# slot_stm32f4.net
KiCad netlist of a schematic drawn in EAGLE
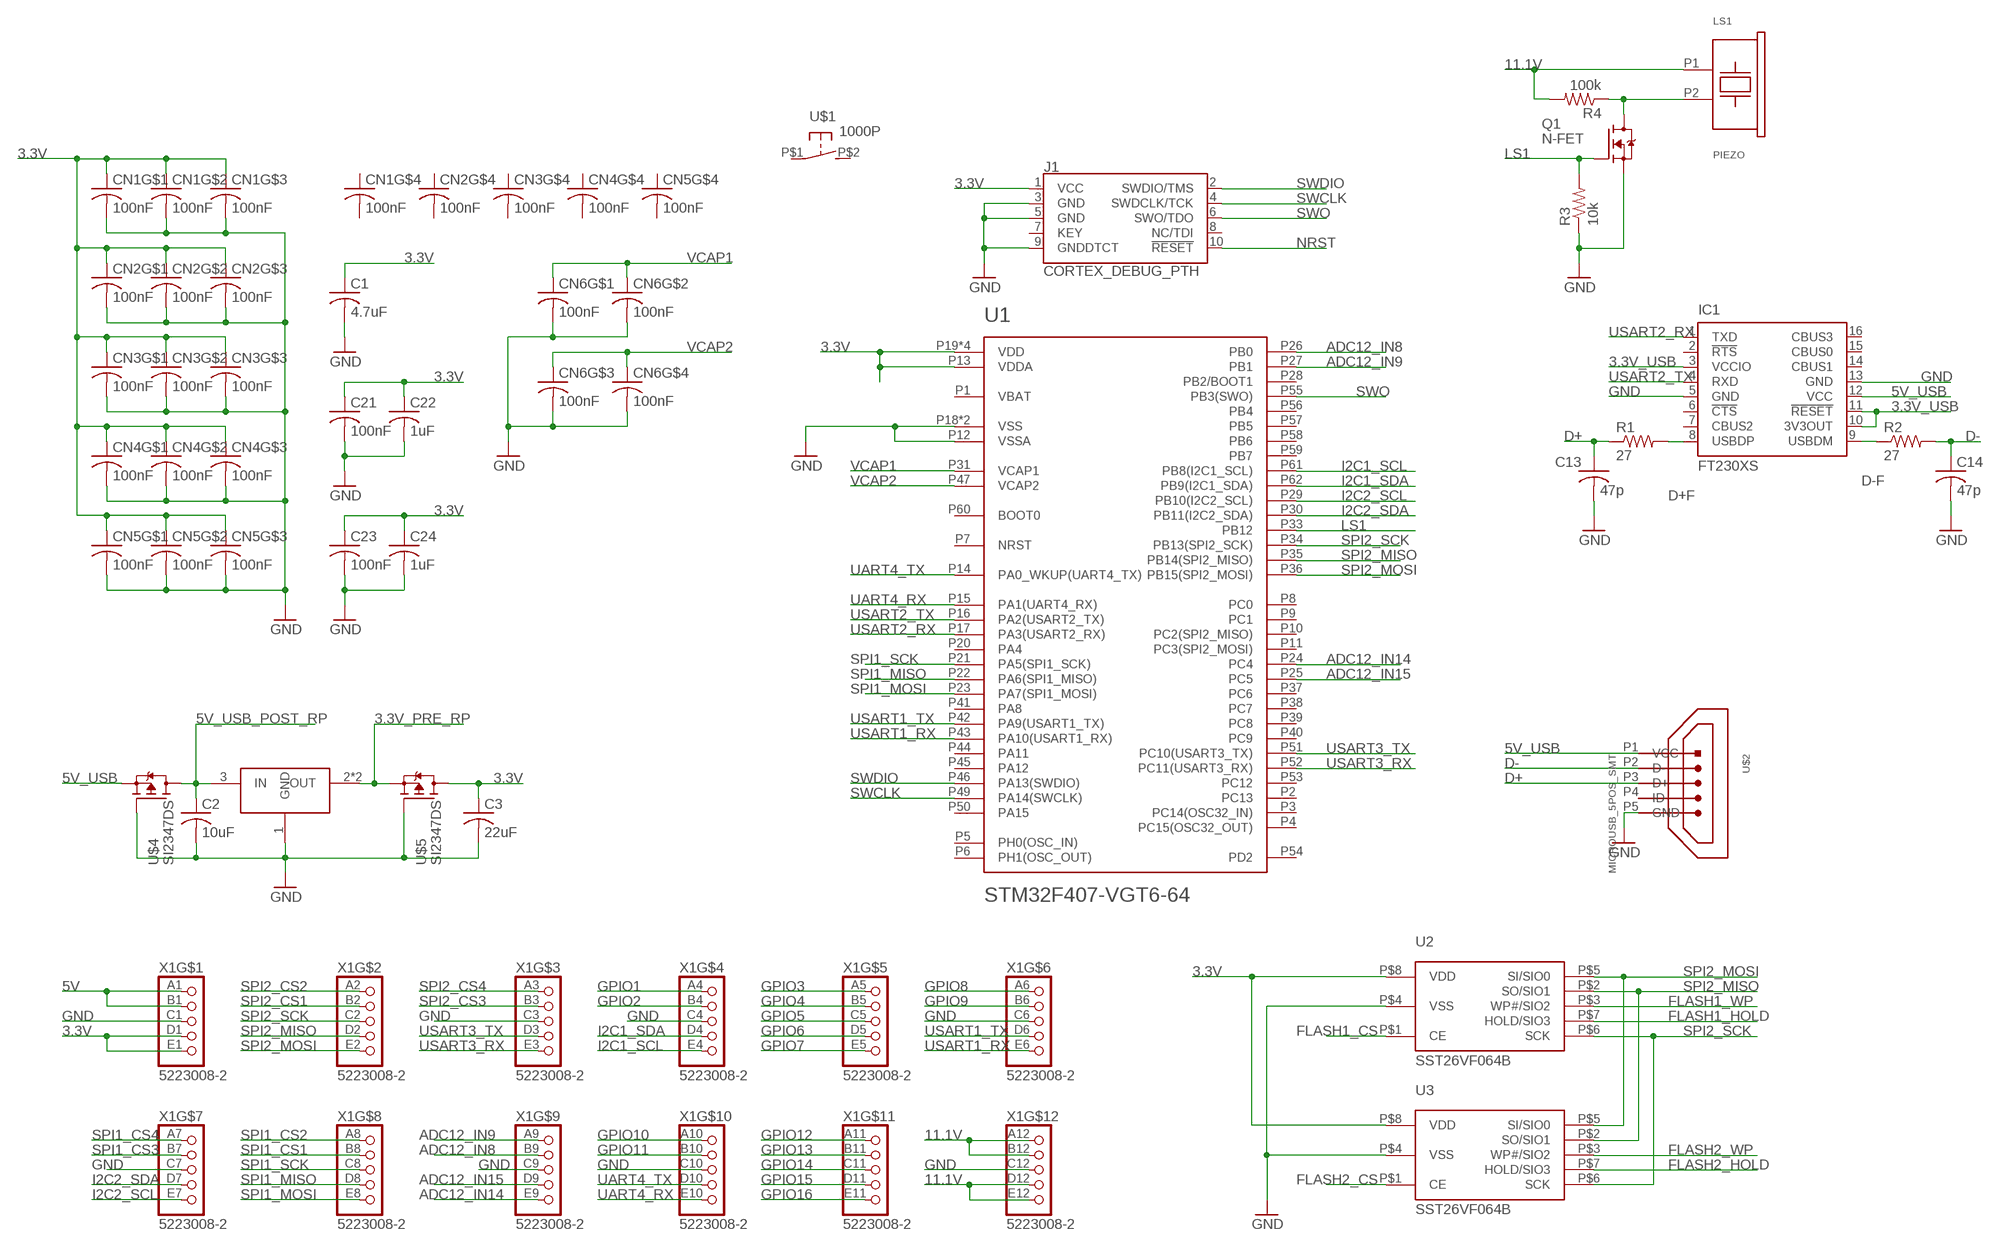
[diagram p0: schematic, sheet 1]

(export (version "E")
  (design (tool "Eeschema 10.0.6"))
  (components
    (comp (ref "C1")
      (value "4.7uF")
      (footprint "eagle-import:C0805")
      (libsource (lib "eagle-import") (part "C-USC0805"))
    )
    (comp (ref "C2")
      (value "10uF")
      (footprint "eagle-import:C0805")
      (libsource (lib "eagle-import") (part "C-USC0805"))
    )
    (comp (ref "C3")
      (value "22uF")
      (footprint "eagle-import:C0805")
      (libsource (lib "eagle-import") (part "C-USC0805"))
    )
    (comp (ref "C13")
      (value "47p")
      (footprint "eagle-import:C0603")
      (libsource (lib "eagle-import") (part "resistor_348_C-USC0603"))
    )
    (comp (ref "C14")
      (value "47p")
      (footprint "eagle-import:C0603")
      (libsource (lib "eagle-import") (part "resistor_348_C-USC0603"))
    )
    (comp (ref "C21")
      (value "100nF")
      (footprint "eagle-import:C0805")
      (libsource (lib "eagle-import") (part "C-USC0805"))
    )
    (comp (ref "C22")
      (value "1uF")
      (footprint "eagle-import:C0805")
      (libsource (lib "eagle-import") (part "C-USC0805"))
    )
    (comp (ref "C23")
      (value "100nF")
      (footprint "eagle-import:C0805")
      (libsource (lib "eagle-import") (part "C-USC0805"))
    )
    (comp (ref "C24")
      (value "1uF")
      (footprint "eagle-import:C0805")
      (libsource (lib "eagle-import") (part "C-USC0805"))
    )
    (comp (ref "CN1")
      (value "100nF")
      (footprint "eagle-import:CNET_4POS_0612")
      (libsource (lib "eagle-import") (part "CA064CXXXXXRAC"))
    )
    (comp (ref "CN2")
      (value "100nF")
      (footprint "eagle-import:CNET_4POS_0612")
      (libsource (lib "eagle-import") (part "CA064CXXXXXRAC"))
    )
    (comp (ref "CN3")
      (value "100nF")
      (footprint "eagle-import:CNET_4POS_0612")
      (libsource (lib "eagle-import") (part "CA064CXXXXXRAC"))
    )
    (comp (ref "CN4")
      (value "100nF")
      (footprint "eagle-import:CNET_4POS_0612")
      (libsource (lib "eagle-import") (part "CA064CXXXXXRAC"))
    )
    (comp (ref "CN5")
      (value "100nF")
      (footprint "eagle-import:CNET_4POS_0612")
      (libsource (lib "eagle-import") (part "CA064CXXXXXRAC"))
    )
    (comp (ref "CN6")
      (value "100nF")
      (footprint "eagle-import:CNET_4POS_0612")
      (libsource (lib "eagle-import") (part "CA064CXXXXXRAC"))
    )
    (comp (ref "IC1")
      (value "FT230XS")
      (footprint "eagle-import:SSOP16")
      (libsource (lib "eagle-import") (part "FT230XS"))
    )
    (comp (ref "J1")
      (value "CORTEX_DEBUG_PTH")
      (footprint "eagle-import:2X5-PTH-1.27MM")
      (libsource (lib "eagle-import") (part "CORTEX_DEBUG_PTH"))
    )
    (comp (ref "LS1")
      (value "PIEZO")
      (footprint "eagle-import:PKMCS0909E400-R1")
      (libsource (lib "eagle-import") (part "PIEZO"))
    )
    (comp (ref "Q1")
      (value "N-FET")
      (footprint "eagle-import:NMINI3-R1-B")
      (libsource (lib "eagle-import") (part "N-FET"))
    )
    (comp (ref "R1")
      (value "27")
      (footprint "eagle-import:R0603")
      (libsource (lib "eagle-import") (part "R-US_R0603"))
    )
    (comp (ref "R2")
      (value "27")
      (footprint "eagle-import:R0603")
      (libsource (lib "eagle-import") (part "R-US_R0603"))
    )
    (comp (ref "R3")
      (value "10k")
      (footprint "eagle-import:R0603")
      (libsource (lib "eagle-import") (part "R-US_R0603"))
    )
    (comp (ref "R4")
      (value "100k")
      (footprint "eagle-import:R0603")
      (libsource (lib "eagle-import") (part "R-US_R0603"))
    )
    (comp (ref "U$1")
      (value "1000P")
      (footprint "eagle-import:B3U-1000P")
      (libsource (lib "eagle-import") (part "1000P"))
    )
    (comp (ref "U$2")
      (value "MICROUSB_5POS_SMT")
      (footprint "eagle-import:RECPT_SMT_R_A")
      (libsource (lib "eagle-import") (part "MICROUSB_5POS_SMT"))
    )
    (comp (ref "U$3")
      (value "AZ1117C")
      (footprint "eagle-import:SOT89")
      (libsource (lib "eagle-import") (part "AZ1117C"))
    )
    (comp (ref "U$4")
      (value "SI2347DS")
      (footprint "eagle-import:SOT23")
      (libsource (lib "eagle-import") (part "SI2347DS"))
    )
    (comp (ref "U$5")
      (value "SI2347DS")
      (footprint "eagle-import:SOT23")
      (libsource (lib "eagle-import") (part "SI2347DS"))
    )
    (comp (ref "U1")
      (value "STM32F407-VGT6-64")
      (footprint "eagle-import:LQFP64")
      (libsource (lib "eagle-import") (part "STM32F407-VGT6-64"))
    )
    (comp (ref "U2")
      (value "SST26VF064B")
      (footprint "eagle-import:SOIJ")
      (libsource (lib "eagle-import") (part "SST26VF064B"))
    )
    (comp (ref "U3")
      (value "SST26VF064B")
      (footprint "eagle-import:SOIJ")
      (libsource (lib "eagle-import") (part "SST26VF064B"))
    )
    (comp (ref "X1")
      (value "5223008-2")
      (footprint "eagle-import:5223008-2")
      (libsource (lib "eagle-import") (part "5223008-2"))
    )
  )
  (nets
    (net (code "1") (name "/3.3V") (class "Default")
      (node (ref "C1") (pin "1") (pinfunction "1_1") (pintype "passive"))
      (node (ref "C21") (pin "1") (pinfunction "1_1") (pintype "passive"))
      (node (ref "C22") (pin "1") (pinfunction "1_1") (pintype "passive"))
      (node (ref "C23") (pin "1") (pinfunction "1_1") (pintype "passive"))
      (node (ref "C24") (pin "1") (pinfunction "1_1") (pintype "passive"))
      (node (ref "C3") (pin "1") (pinfunction "1_1") (pintype "passive"))
      (node (ref "CN1") (pin "C1A") (pinfunction "1_C1A") (pintype "passive"))
      (node (ref "CN1") (pin "C2A") (pinfunction "1_C2A") (pintype "passive"))
      (node (ref "CN1") (pin "C3A") (pinfunction "1_C3A") (pintype "passive"))
      (node (ref "CN2") (pin "C1A") (pinfunction "1_C1A") (pintype "passive"))
      (node (ref "CN2") (pin "C2A") (pinfunction "1_C2A") (pintype "passive"))
      (node (ref "CN2") (pin "C3A") (pinfunction "1_C3A") (pintype "passive"))
      (node (ref "CN3") (pin "C1A") (pinfunction "1_C1A") (pintype "passive"))
      (node (ref "CN3") (pin "C2A") (pinfunction "1_C2A") (pintype "passive"))
      (node (ref "CN3") (pin "C3A") (pinfunction "1_C3A") (pintype "passive"))
      (node (ref "CN4") (pin "C1A") (pinfunction "1_C1A") (pintype "passive"))
      (node (ref "CN4") (pin "C2A") (pinfunction "1_C2A") (pintype "passive"))
      (node (ref "CN4") (pin "C3A") (pinfunction "1_C3A") (pintype "passive"))
      (node (ref "CN5") (pin "C1A") (pinfunction "1_C1A") (pintype "passive"))
      (node (ref "CN5") (pin "C2A") (pinfunction "1_C2A") (pintype "passive"))
      (node (ref "CN5") (pin "C3A") (pinfunction "1_C3A") (pintype "passive"))
      (node (ref "J1") (pin "1") (pinfunction "VCC_1") (pintype "bidirectional"))
      (node (ref "U$5") (pin "3") (pinfunction "D_3") (pintype "passive"))
      (node (ref "U1") (pin "P13") (pinfunction "VDDA_P13") (pintype "bidirectional"))
      (node (ref "U1") (pin "P19") (pinfunction "VDD_P19") (pintype "bidirectional"))
      (node (ref "U1") (pin "P32") (pinfunction "VDD_P32") (pintype "bidirectional"))
      (node (ref "U1") (pin "P48") (pinfunction "VDD_P48") (pintype "bidirectional"))
      (node (ref "U1") (pin "P64") (pinfunction "VDD_P64") (pintype "bidirectional"))
      (node (ref "U2") (pin "P$8") (pinfunction "VDD_P$8") (pintype "bidirectional"))
      (node (ref "U3") (pin "P$8") (pinfunction "VDD_P$8") (pintype "bidirectional"))
      (node (ref "X1") (pin "D1") (pinfunction "4_D1") (pintype "passive"))
      (node (ref "X1") (pin "E1") (pinfunction "5_E1") (pintype "passive"))
    )
    (net (code "2") (name "/3.3V_PRE_RP") (class "Default")
      (node (ref "U$3") (pin "2") (pinfunction "OUT_2") (pintype "bidirectional"))
      (node (ref "U$3") (pin "2@1") (pinfunction "OUT_2@1") (pintype "bidirectional"))
      (node (ref "U$5") (pin "2") (pinfunction "S_2") (pintype "passive"))
    )
    (net (code "3") (name "/3.3V_USB") (class "Default")
      (node (ref "IC1") (pin "10") (pinfunction "3V3OUT_10") (pintype "output"))
      (node (ref "IC1") (pin "11") (pinfunction "~{RESET}_11") (pintype "input"))
      (node (ref "IC1") (pin "3") (pinfunction "VCCIO_3") (pintype "power_in"))
    )
    (net (code "4") (name "/5V") (class "Default")
      (node (ref "X1") (pin "A1") (pinfunction "1_A1") (pintype "passive"))
      (node (ref "X1") (pin "B1") (pinfunction "2_B1") (pintype "passive"))
    )
    (net (code "5") (name "/5V_USB") (class "Default")
      (node (ref "IC1") (pin "12") (pinfunction "VCC_12") (pintype "power_in"))
      (node (ref "U$2") (pin "P1") (pinfunction "VCC_P1") (pintype "bidirectional"))
      (node (ref "U$4") (pin "2") (pinfunction "S_2") (pintype "passive"))
    )
    (net (code "6") (name "/5V_USB_POST_RP") (class "Default")
      (node (ref "C2") (pin "1") (pinfunction "1_1") (pintype "passive"))
      (node (ref "U$3") (pin "3") (pinfunction "IN_3") (pintype "bidirectional"))
      (node (ref "U$4") (pin "3") (pinfunction "D_3") (pintype "passive"))
    )
    (net (code "7") (name "/11.1V") (class "Default")
      (node (ref "LS1") (pin "P1") (pinfunction "P1_P1") (pintype "bidirectional"))
      (node (ref "R4") (pin "2") (pinfunction "2_2") (pintype "passive"))
      (node (ref "X1") (pin "A12") (pinfunction "1_A12") (pintype "passive"))
      (node (ref "X1") (pin "B12") (pinfunction "2_B12") (pintype "passive"))
      (node (ref "X1") (pin "D12") (pinfunction "4_D12") (pintype "passive"))
      (node (ref "X1") (pin "E12") (pinfunction "5_E12") (pintype "passive"))
    )
    (net (code "8") (name "/ADC12_IN8") (class "Default")
      (node (ref "U1") (pin "P26") (pinfunction "PB0_P26") (pintype "bidirectional"))
      (node (ref "X1") (pin "B9") (pinfunction "2_B9") (pintype "passive"))
    )
    (net (code "9") (name "/ADC12_IN9") (class "Default")
      (node (ref "U1") (pin "P27") (pinfunction "PB1_P27") (pintype "bidirectional"))
      (node (ref "X1") (pin "A9") (pinfunction "1_A9") (pintype "passive"))
    )
    (net (code "10") (name "/ADC12_IN14") (class "Default")
      (node (ref "U1") (pin "P24") (pinfunction "PC4_P24") (pintype "bidirectional"))
      (node (ref "X1") (pin "E9") (pinfunction "5_E9") (pintype "passive"))
    )
    (net (code "11") (name "/ADC12_IN15") (class "Default")
      (node (ref "U1") (pin "P25") (pinfunction "PC5_P25") (pintype "bidirectional"))
      (node (ref "X1") (pin "D9") (pinfunction "4_D9") (pintype "passive"))
    )
    (net (code "12") (name "/D+") (class "Default")
      (node (ref "C13") (pin "1") (pinfunction "1_1") (pintype "passive"))
      (node (ref "R1") (pin "1") (pinfunction "1_1") (pintype "passive"))
      (node (ref "U$2") (pin "P3") (pinfunction "D+_P3") (pintype "bidirectional"))
    )
    (net (code "13") (name "/D+F") (class "Default")
      (node (ref "IC1") (pin "8") (pinfunction "USBDP_8") (pintype "input"))
      (node (ref "R1") (pin "2") (pinfunction "2_2") (pintype "passive"))
    )
    (net (code "14") (name "/D-") (class "Default")
      (node (ref "C14") (pin "1") (pinfunction "1_1") (pintype "passive"))
      (node (ref "R2") (pin "2") (pinfunction "2_2") (pintype "passive"))
      (node (ref "U$2") (pin "P2") (pinfunction "D-_P2") (pintype "bidirectional"))
    )
    (net (code "15") (name "/D-F") (class "Default")
      (node (ref "IC1") (pin "9") (pinfunction "USBDM_9") (pintype "input"))
      (node (ref "R2") (pin "1") (pinfunction "1_1") (pintype "passive"))
    )
    (net (code "16") (name "/FLASH1_CS") (class "Default")
      (node (ref "U2") (pin "P$1") (pinfunction "CE_P$1") (pintype "bidirectional"))
    )
    (net (code "17") (name "/FLASH1_HOLD") (class "Default")
      (node (ref "U2") (pin "P$7") (pinfunction "HOLD/SIO3_P$7") (pintype "bidirectional"))
    )
    (net (code "18") (name "/FLASH1_WP") (class "Default")
      (node (ref "U2") (pin "P$3") (pinfunction "WP#/SIO2_P$3") (pintype "bidirectional"))
    )
    (net (code "19") (name "/FLASH2_CS") (class "Default")
      (node (ref "U3") (pin "P$1") (pinfunction "CE_P$1") (pintype "bidirectional"))
    )
    (net (code "20") (name "/FLASH2_HOLD") (class "Default")
      (node (ref "U3") (pin "P$7") (pinfunction "HOLD/SIO3_P$7") (pintype "bidirectional"))
    )
    (net (code "21") (name "/FLASH2_WP") (class "Default")
      (node (ref "U3") (pin "P$3") (pinfunction "WP#/SIO2_P$3") (pintype "bidirectional"))
    )
    (net (code "22") (name "/GPIO1") (class "Default")
      (node (ref "X1") (pin "A4") (pinfunction "1_A4") (pintype "passive"))
    )
    (net (code "23") (name "/GPIO2") (class "Default")
      (node (ref "X1") (pin "B4") (pinfunction "2_B4") (pintype "passive"))
    )
    (net (code "24") (name "/GPIO3") (class "Default")
      (node (ref "X1") (pin "A5") (pinfunction "1_A5") (pintype "passive"))
    )
    (net (code "25") (name "/GPIO4") (class "Default")
      (node (ref "X1") (pin "B5") (pinfunction "2_B5") (pintype "passive"))
    )
    (net (code "26") (name "/GPIO5") (class "Default")
      (node (ref "X1") (pin "C5") (pinfunction "3_C5") (pintype "passive"))
    )
    (net (code "27") (name "/GPIO6") (class "Default")
      (node (ref "X1") (pin "D5") (pinfunction "4_D5") (pintype "passive"))
    )
    (net (code "28") (name "/GPIO7") (class "Default")
      (node (ref "X1") (pin "E5") (pinfunction "5_E5") (pintype "passive"))
    )
    (net (code "29") (name "/GPIO8") (class "Default")
      (node (ref "X1") (pin "A6") (pinfunction "1_A6") (pintype "passive"))
    )
    (net (code "30") (name "/GPIO9") (class "Default")
      (node (ref "X1") (pin "B6") (pinfunction "2_B6") (pintype "passive"))
    )
    (net (code "31") (name "/GPIO10") (class "Default")
      (node (ref "X1") (pin "A10") (pinfunction "1_A10") (pintype "passive"))
    )
    (net (code "32") (name "/GPIO11") (class "Default")
      (node (ref "X1") (pin "B10") (pinfunction "2_B10") (pintype "passive"))
    )
    (net (code "33") (name "/GPIO12") (class "Default")
      (node (ref "X1") (pin "A11") (pinfunction "1_A11") (pintype "passive"))
    )
    (net (code "34") (name "/GPIO13") (class "Default")
      (node (ref "X1") (pin "B11") (pinfunction "2_B11") (pintype "passive"))
    )
    (net (code "35") (name "/GPIO14") (class "Default")
      (node (ref "X1") (pin "C11") (pinfunction "3_C11") (pintype "passive"))
    )
    (net (code "36") (name "/GPIO15") (class "Default")
      (node (ref "X1") (pin "D11") (pinfunction "4_D11") (pintype "passive"))
    )
    (net (code "37") (name "/GPIO16") (class "Default")
      (node (ref "X1") (pin "E11") (pinfunction "5_E11") (pintype "passive"))
    )
    (net (code "38") (name "/I2C1_SCL") (class "Default")
      (node (ref "U1") (pin "P61") (pinfunction "PB8(I2C1_SCL)_P61") (pintype "bidirectional"))
      (node (ref "X1") (pin "E4") (pinfunction "5_E4") (pintype "passive"))
    )
    (net (code "39") (name "/I2C1_SDA") (class "Default")
      (node (ref "U1") (pin "P62") (pinfunction "PB9(I2C1_SDA)_P62") (pintype "bidirectional"))
      (node (ref "X1") (pin "D4") (pinfunction "4_D4") (pintype "passive"))
    )
    (net (code "40") (name "/I2C2_SCL") (class "Default")
      (node (ref "U1") (pin "P29") (pinfunction "PB10(I2C2_SCL)_P29") (pintype "bidirectional"))
      (node (ref "X1") (pin "E7") (pinfunction "5_E7") (pintype "passive"))
    )
    (net (code "41") (name "/I2C2_SDA") (class "Default")
      (node (ref "U1") (pin "P30") (pinfunction "PB11(I2C2_SDA)_P30") (pintype "bidirectional"))
      (node (ref "X1") (pin "D7") (pinfunction "4_D7") (pintype "passive"))
    )
    (net (code "42") (name "/LS1") (class "Default")
      (node (ref "Q1") (pin "2") (pinfunction "G_2") (pintype "passive"))
      (node (ref "R3") (pin "2") (pinfunction "2_2") (pintype "passive"))
      (node (ref "U1") (pin "P33") (pinfunction "PB12_P33") (pintype "bidirectional"))
    )
    (net (code "43") (name "/NRST") (class "Default")
      (node (ref "J1") (pin "10") (pinfunction "~{RESET}_10") (pintype "bidirectional"))
    )
    (net (code "44") (name "/SPI1_CS1") (class "Default")
      (node (ref "X1") (pin "B8") (pinfunction "2_B8") (pintype "passive"))
    )
    (net (code "45") (name "/SPI1_CS2") (class "Default")
      (node (ref "X1") (pin "A8") (pinfunction "1_A8") (pintype "passive"))
    )
    (net (code "46") (name "/SPI1_CS3") (class "Default")
      (node (ref "X1") (pin "B7") (pinfunction "2_B7") (pintype "passive"))
    )
    (net (code "47") (name "/SPI1_CS4") (class "Default")
      (node (ref "X1") (pin "A7") (pinfunction "1_A7") (pintype "passive"))
    )
    (net (code "48") (name "/SPI1_MISO") (class "Default")
      (node (ref "U1") (pin "P22") (pinfunction "PA6(SPI1_MISO)_P22") (pintype "bidirectional"))
      (node (ref "X1") (pin "D8") (pinfunction "4_D8") (pintype "passive"))
    )
    (net (code "49") (name "/SPI1_MOSI") (class "Default")
      (node (ref "U1") (pin "P23") (pinfunction "PA7(SPI1_MOSI)_P23") (pintype "bidirectional"))
      (node (ref "X1") (pin "E8") (pinfunction "5_E8") (pintype "passive"))
    )
    (net (code "50") (name "/SPI1_SCK") (class "Default")
      (node (ref "U1") (pin "P21") (pinfunction "PA5(SPI1_SCK)_P21") (pintype "bidirectional"))
      (node (ref "X1") (pin "C8") (pinfunction "3_C8") (pintype "passive"))
    )
    (net (code "51") (name "/SPI2_CS1") (class "Default")
      (node (ref "X1") (pin "B2") (pinfunction "2_B2") (pintype "passive"))
    )
    (net (code "52") (name "/SPI2_CS2") (class "Default")
      (node (ref "X1") (pin "A2") (pinfunction "1_A2") (pintype "passive"))
    )
    (net (code "53") (name "/SPI2_CS3") (class "Default")
      (node (ref "X1") (pin "B3") (pinfunction "2_B3") (pintype "passive"))
    )
    (net (code "54") (name "/SPI2_CS4") (class "Default")
      (node (ref "X1") (pin "A3") (pinfunction "1_A3") (pintype "passive"))
    )
    (net (code "55") (name "/SPI2_MISO") (class "Default")
      (node (ref "U1") (pin "P35") (pinfunction "PB14(SPI2_MISO)_P35") (pintype "bidirectional"))
      (node (ref "U2") (pin "P$2") (pinfunction "SO/SIO1_P$2") (pintype "bidirectional"))
      (node (ref "U3") (pin "P$2") (pinfunction "SO/SIO1_P$2") (pintype "bidirectional"))
      (node (ref "X1") (pin "D2") (pinfunction "4_D2") (pintype "passive"))
    )
    (net (code "56") (name "/SPI2_MOSI") (class "Default")
      (node (ref "U1") (pin "P36") (pinfunction "PB15(SPI2_MOSI)_P36") (pintype "bidirectional"))
      (node (ref "U2") (pin "P$5") (pinfunction "SI/SIO0_P$5") (pintype "bidirectional"))
      (node (ref "U3") (pin "P$5") (pinfunction "SI/SIO0_P$5") (pintype "bidirectional"))
      (node (ref "X1") (pin "E2") (pinfunction "5_E2") (pintype "passive"))
    )
    (net (code "57") (name "/SPI2_SCK") (class "Default")
      (node (ref "U1") (pin "P34") (pinfunction "PB13(SPI2_SCK)_P34") (pintype "bidirectional"))
      (node (ref "U2") (pin "P$6") (pinfunction "SCK_P$6") (pintype "bidirectional"))
      (node (ref "U3") (pin "P$6") (pinfunction "SCK_P$6") (pintype "bidirectional"))
      (node (ref "X1") (pin "C2") (pinfunction "3_C2") (pintype "passive"))
    )
    (net (code "58") (name "/SWCLK") (class "Default")
      (node (ref "J1") (pin "4") (pinfunction "SWDCLK/TCK_4") (pintype "bidirectional"))
      (node (ref "U1") (pin "P49") (pinfunction "PA14(SWCLK)_P49") (pintype "bidirectional"))
    )
    (net (code "59") (name "/SWDIO") (class "Default")
      (node (ref "J1") (pin "2") (pinfunction "SWDIO/TMS_2") (pintype "bidirectional"))
      (node (ref "U1") (pin "P46") (pinfunction "PA13(SWDIO)_P46") (pintype "bidirectional"))
    )
    (net (code "60") (name "/SWO") (class "Default")
      (node (ref "J1") (pin "6") (pinfunction "SWO/TDO_6") (pintype "bidirectional"))
      (node (ref "U1") (pin "P55") (pinfunction "PB3(SWO)_P55") (pintype "bidirectional"))
    )
    (net (code "61") (name "/UART4_RX") (class "Default")
      (node (ref "U1") (pin "P15") (pinfunction "PA1(UART4_RX)_P15") (pintype "bidirectional"))
      (node (ref "X1") (pin "E10") (pinfunction "5_E10") (pintype "passive"))
    )
    (net (code "62") (name "/UART4_TX") (class "Default")
      (node (ref "U1") (pin "P14") (pinfunction "PA0_WKUP(UART4_TX)_P14") (pintype "bidirectional"))
      (node (ref "X1") (pin "D10") (pinfunction "4_D10") (pintype "passive"))
    )
    (net (code "63") (name "/USART1_RX") (class "Default")
      (node (ref "U1") (pin "P43") (pinfunction "PA10(USART1_RX)_P43") (pintype "bidirectional"))
      (node (ref "X1") (pin "E6") (pinfunction "5_E6") (pintype "passive"))
    )
    (net (code "64") (name "/USART1_TX") (class "Default")
      (node (ref "U1") (pin "P42") (pinfunction "PA9(USART1_TX)_P42") (pintype "bidirectional"))
      (node (ref "X1") (pin "D6") (pinfunction "4_D6") (pintype "passive"))
    )
    (net (code "65") (name "/USART2_RX") (class "Default")
      (node (ref "IC1") (pin "1") (pinfunction "TXD_1") (pintype "output"))
      (node (ref "U1") (pin "P17") (pinfunction "PA3(USART2_RX)_P17") (pintype "bidirectional"))
    )
    (net (code "66") (name "/USART2_TX") (class "Default")
      (node (ref "IC1") (pin "4") (pinfunction "RXD_4") (pintype "input"))
      (node (ref "U1") (pin "P16") (pinfunction "PA2(USART2_TX)_P16") (pintype "bidirectional"))
    )
    (net (code "67") (name "/USART3_RX") (class "Default")
      (node (ref "U1") (pin "P52") (pinfunction "PC11(USART3_RX)_P52") (pintype "bidirectional"))
      (node (ref "X1") (pin "E3") (pinfunction "5_E3") (pintype "passive"))
    )
    (net (code "68") (name "/USART3_TX") (class "Default")
      (node (ref "U1") (pin "P51") (pinfunction "PC10(USART3_TX)_P51") (pintype "bidirectional"))
      (node (ref "X1") (pin "D3") (pinfunction "4_D3") (pintype "passive"))
    )
    (net (code "69") (name "/VCAP1") (class "Default")
      (node (ref "CN6") (pin "C1A") (pinfunction "1_C1A") (pintype "passive"))
      (node (ref "CN6") (pin "C2A") (pinfunction "1_C2A") (pintype "passive"))
      (node (ref "U1") (pin "P31") (pinfunction "VCAP1_P31") (pintype "bidirectional"))
    )
    (net (code "70") (name "/VCAP2") (class "Default")
      (node (ref "CN6") (pin "C3A") (pinfunction "1_C3A") (pintype "passive"))
      (node (ref "CN6") (pin "C4A") (pinfunction "1_C4A") (pintype "passive"))
      (node (ref "U1") (pin "P47") (pinfunction "VCAP2_P47") (pintype "bidirectional"))
    )
    (net (code "71") (name "GND") (class "Default")
      (node (ref "C1") (pin "2") (pinfunction "2_2") (pintype "passive"))
      (node (ref "C13") (pin "2") (pinfunction "2_2") (pintype "passive"))
      (node (ref "C14") (pin "2") (pinfunction "2_2") (pintype "passive"))
      (node (ref "C2") (pin "2") (pinfunction "2_2") (pintype "passive"))
      (node (ref "C21") (pin "2") (pinfunction "2_2") (pintype "passive"))
      (node (ref "C22") (pin "2") (pinfunction "2_2") (pintype "passive"))
      (node (ref "C23") (pin "2") (pinfunction "2_2") (pintype "passive"))
      (node (ref "C24") (pin "2") (pinfunction "2_2") (pintype "passive"))
      (node (ref "C3") (pin "2") (pinfunction "2_2") (pintype "passive"))
      (node (ref "CN1") (pin "C1B") (pinfunction "2_C1B") (pintype "passive"))
      (node (ref "CN1") (pin "C2B") (pinfunction "2_C2B") (pintype "passive"))
      (node (ref "CN1") (pin "C3B") (pinfunction "2_C3B") (pintype "passive"))
      (node (ref "CN2") (pin "C1B") (pinfunction "2_C1B") (pintype "passive"))
      (node (ref "CN2") (pin "C2B") (pinfunction "2_C2B") (pintype "passive"))
      (node (ref "CN2") (pin "C3B") (pinfunction "2_C3B") (pintype "passive"))
      (node (ref "CN3") (pin "C1B") (pinfunction "2_C1B") (pintype "passive"))
      (node (ref "CN3") (pin "C2B") (pinfunction "2_C2B") (pintype "passive"))
      (node (ref "CN3") (pin "C3B") (pinfunction "2_C3B") (pintype "passive"))
      (node (ref "CN4") (pin "C1B") (pinfunction "2_C1B") (pintype "passive"))
      (node (ref "CN4") (pin "C2B") (pinfunction "2_C2B") (pintype "passive"))
      (node (ref "CN4") (pin "C3B") (pinfunction "2_C3B") (pintype "passive"))
      (node (ref "CN5") (pin "C1B") (pinfunction "2_C1B") (pintype "passive"))
      (node (ref "CN5") (pin "C2B") (pinfunction "2_C2B") (pintype "passive"))
      (node (ref "CN5") (pin "C3B") (pinfunction "2_C3B") (pintype "passive"))
      (node (ref "CN6") (pin "C1B") (pinfunction "2_C1B") (pintype "passive"))
      (node (ref "CN6") (pin "C2B") (pinfunction "2_C2B") (pintype "passive"))
      (node (ref "CN6") (pin "C3B") (pinfunction "2_C3B") (pintype "passive"))
      (node (ref "CN6") (pin "C4B") (pinfunction "2_C4B") (pintype "passive"))
      (node (ref "IC1") (pin "13") (pinfunction "GND_13") (pintype "power_in"))
      (node (ref "IC1") (pin "5") (pinfunction "GND_5") (pintype "power_in"))
      (node (ref "J1") (pin "3") (pinfunction "GND_3") (pintype "bidirectional"))
      (node (ref "J1") (pin "5") (pinfunction "GND_5") (pintype "bidirectional"))
      (node (ref "J1") (pin "9") (pinfunction "GNDDTCT_9") (pintype "bidirectional"))
      (node (ref "Q1") (pin "3") (pinfunction "S_3") (pintype "passive"))
      (node (ref "R3") (pin "1") (pinfunction "1_1") (pintype "passive"))
      (node (ref "U$2") (pin "P5") (pinfunction "GND_P5") (pintype "bidirectional"))
      (node (ref "U$3") (pin "1") (pinfunction "GND_1") (pintype "bidirectional"))
      (node (ref "U$4") (pin "1") (pinfunction "G_1") (pintype "passive"))
      (node (ref "U$5") (pin "1") (pinfunction "G_1") (pintype "passive"))
      (node (ref "U1") (pin "P12") (pinfunction "VSSA_P12") (pintype "bidirectional"))
      (node (ref "U1") (pin "P18") (pinfunction "VSS_P18") (pintype "bidirectional"))
      (node (ref "U1") (pin "P63") (pinfunction "VSS_P63") (pintype "bidirectional"))
      (node (ref "U2") (pin "P$4") (pinfunction "VSS_P$4") (pintype "bidirectional"))
      (node (ref "U3") (pin "P$4") (pinfunction "VSS_P$4") (pintype "bidirectional"))
      (node (ref "X1") (pin "C1") (pinfunction "3_C1") (pintype "passive"))
      (node (ref "X1") (pin "C10") (pinfunction "3_C10") (pintype "passive"))
      (node (ref "X1") (pin "C12") (pinfunction "3_C12") (pintype "passive"))
      (node (ref "X1") (pin "C3") (pinfunction "3_C3") (pintype "passive"))
      (node (ref "X1") (pin "C4") (pinfunction "3_C4") (pintype "passive"))
      (node (ref "X1") (pin "C6") (pinfunction "3_C6") (pintype "passive"))
      (node (ref "X1") (pin "C7") (pinfunction "3_C7") (pintype "passive"))
      (node (ref "X1") (pin "C9") (pinfunction "3_C9") (pintype "passive"))
    )
    (net (code "72") (name "Net-(Q1-D)") (class "Default")
      (node (ref "LS1") (pin "P2") (pinfunction "P2_P2") (pintype "bidirectional"))
      (node (ref "Q1") (pin "1") (pinfunction "D_1") (pintype "passive"))
      (node (ref "R4") (pin "1") (pinfunction "1_1") (pintype "passive"))
    )
    (net (code "73") (name "unconnected-(CN1D-1-PadC4A)") (class "Default")
      (node (ref "CN1") (pin "C4A") (pinfunction "1_C4A") (pintype "passive"))
    )
    (net (code "74") (name "unconnected-(CN1D-2-PadC4B)") (class "Default")
      (node (ref "CN1") (pin "C4B") (pinfunction "2_C4B") (pintype "passive"))
    )
    (net (code "75") (name "unconnected-(CN2D-1-PadC4A)") (class "Default")
      (node (ref "CN2") (pin "C4A") (pinfunction "1_C4A") (pintype "passive"))
    )
    (net (code "76") (name "unconnected-(CN2D-2-PadC4B)") (class "Default")
      (node (ref "CN2") (pin "C4B") (pinfunction "2_C4B") (pintype "passive"))
    )
    (net (code "77") (name "unconnected-(CN3D-1-PadC4A)") (class "Default")
      (node (ref "CN3") (pin "C4A") (pinfunction "1_C4A") (pintype "passive"))
    )
    (net (code "78") (name "unconnected-(CN3D-2-PadC4B)") (class "Default")
      (node (ref "CN3") (pin "C4B") (pinfunction "2_C4B") (pintype "passive"))
    )
    (net (code "79") (name "unconnected-(CN4D-1-PadC4A)") (class "Default")
      (node (ref "CN4") (pin "C4A") (pinfunction "1_C4A") (pintype "passive"))
    )
    (net (code "80") (name "unconnected-(CN4D-2-PadC4B)") (class "Default")
      (node (ref "CN4") (pin "C4B") (pinfunction "2_C4B") (pintype "passive"))
    )
    (net (code "81") (name "unconnected-(CN5D-1-PadC4A)") (class "Default")
      (node (ref "CN5") (pin "C4A") (pinfunction "1_C4A") (pintype "passive"))
    )
    (net (code "82") (name "unconnected-(CN5D-2-PadC4B)") (class "Default")
      (node (ref "CN5") (pin "C4B") (pinfunction "2_C4B") (pintype "passive"))
    )
    (net (code "83") (name "unconnected-(IC1-CBUS0-Pad15)") (class "Default")
      (node (ref "IC1") (pin "15") (pinfunction "CBUS0_15") (pintype "bidirectional"))
    )
    (net (code "84") (name "unconnected-(IC1-CBUS1-Pad14)") (class "Default")
      (node (ref "IC1") (pin "14") (pinfunction "CBUS1_14") (pintype "bidirectional"))
    )
    (net (code "85") (name "unconnected-(IC1-CBUS2-Pad7)") (class "Default")
      (node (ref "IC1") (pin "7") (pinfunction "CBUS2_7") (pintype "bidirectional"))
    )
    (net (code "86") (name "unconnected-(IC1-CBUS3-Pad16)") (class "Default")
      (node (ref "IC1") (pin "16") (pinfunction "CBUS3_16") (pintype "bidirectional"))
    )
    (net (code "87") (name "unconnected-(IC1-~{CTS}-Pad6)") (class "Default")
      (node (ref "IC1") (pin "6") (pinfunction "~{CTS}_6") (pintype "input"))
    )
    (net (code "88") (name "unconnected-(IC1-~{RTS}-Pad2)") (class "Default")
      (node (ref "IC1") (pin "2") (pinfunction "~{RTS}_2") (pintype "output"))
    )
    (net (code "89") (name "unconnected-(J1-KEY-Pad7)") (class "Default")
      (node (ref "J1") (pin "7") (pinfunction "KEY_7") (pintype "bidirectional"))
    )
    (net (code "90") (name "unconnected-(J1-NC{slash}TDI-Pad8)") (class "Default")
      (node (ref "J1") (pin "8") (pinfunction "NC/TDI_8") (pintype "bidirectional"))
    )
    (net (code "91") (name "unconnected-(U$1-P-PadP$1)") (class "Default")
      (node (ref "U$1") (pin "P$1") (pinfunction "P_P$1") (pintype "passive"))
    )
    (net (code "92") (name "unconnected-(U$1-S-PadP$2)") (class "Default")
      (node (ref "U$1") (pin "P$2") (pinfunction "S_P$2") (pintype "passive"))
    )
    (net (code "93") (name "unconnected-(U$2-ID-PadP4)") (class "Default")
      (node (ref "U$2") (pin "P4") (pinfunction "ID_P4") (pintype "bidirectional"))
    )
    (net (code "94") (name "unconnected-(U1-BOOT0-PadP60)") (class "Default")
      (node (ref "U1") (pin "P60") (pinfunction "BOOT0_P60") (pintype "bidirectional"))
    )
    (net (code "95") (name "unconnected-(U1-NRST-PadP7)") (class "Default")
      (node (ref "U1") (pin "P7") (pinfunction "NRST_P7") (pintype "bidirectional"))
    )
    (net (code "96") (name "unconnected-(U1-PA4-PadP20)") (class "Default")
      (node (ref "U1") (pin "P20") (pinfunction "PA4_P20") (pintype "bidirectional"))
    )
    (net (code "97") (name "unconnected-(U1-PA8-PadP41)") (class "Default")
      (node (ref "U1") (pin "P41") (pinfunction "PA8_P41") (pintype "bidirectional"))
    )
    (net (code "98") (name "unconnected-(U1-PA11-PadP44)") (class "Default")
      (node (ref "U1") (pin "P44") (pinfunction "PA11_P44") (pintype "bidirectional"))
    )
    (net (code "99") (name "unconnected-(U1-PA12-PadP45)") (class "Default")
      (node (ref "U1") (pin "P45") (pinfunction "PA12_P45") (pintype "bidirectional"))
    )
    (net (code "100") (name "unconnected-(U1-PA15-PadP50)") (class "Default")
      (node (ref "U1") (pin "P50") (pinfunction "PA15_P50") (pintype "bidirectional"))
    )
    (net (code "101") (name "unconnected-(U1-PB2{slash}BOOT1-PadP28)") (class "Default")
      (node (ref "U1") (pin "P28") (pinfunction "PB2/BOOT1_P28") (pintype "bidirectional"))
    )
    (net (code "102") (name "unconnected-(U1-PB4-PadP56)") (class "Default")
      (node (ref "U1") (pin "P56") (pinfunction "PB4_P56") (pintype "bidirectional"))
    )
    (net (code "103") (name "unconnected-(U1-PB5-PadP57)") (class "Default")
      (node (ref "U1") (pin "P57") (pinfunction "PB5_P57") (pintype "bidirectional"))
    )
    (net (code "104") (name "unconnected-(U1-PB6-PadP58)") (class "Default")
      (node (ref "U1") (pin "P58") (pinfunction "PB6_P58") (pintype "bidirectional"))
    )
    (net (code "105") (name "unconnected-(U1-PB7-PadP59)") (class "Default")
      (node (ref "U1") (pin "P59") (pinfunction "PB7_P59") (pintype "bidirectional"))
    )
    (net (code "106") (name "unconnected-(U1-PC0-PadP8)") (class "Default")
      (node (ref "U1") (pin "P8") (pinfunction "PC0_P8") (pintype "bidirectional"))
    )
    (net (code "107") (name "unconnected-(U1-PC1-PadP9)") (class "Default")
      (node (ref "U1") (pin "P9") (pinfunction "PC1_P9") (pintype "bidirectional"))
    )
    (net (code "108") (name "unconnected-(U1-PC2(SPI2_MISO)-PadP10)") (class "Default")
      (node (ref "U1") (pin "P10") (pinfunction "PC2(SPI2_MISO)_P10") (pintype "bidirectional"))
    )
    (net (code "109") (name "unconnected-(U1-PC3(SPI2_MOSI)-PadP11)") (class "Default")
      (node (ref "U1") (pin "P11") (pinfunction "PC3(SPI2_MOSI)_P11") (pintype "bidirectional"))
    )
    (net (code "110") (name "unconnected-(U1-PC6-PadP37)") (class "Default")
      (node (ref "U1") (pin "P37") (pinfunction "PC6_P37") (pintype "bidirectional"))
    )
    (net (code "111") (name "unconnected-(U1-PC7-PadP38)") (class "Default")
      (node (ref "U1") (pin "P38") (pinfunction "PC7_P38") (pintype "bidirectional"))
    )
    (net (code "112") (name "unconnected-(U1-PC8-PadP39)") (class "Default")
      (node (ref "U1") (pin "P39") (pinfunction "PC8_P39") (pintype "bidirectional"))
    )
    (net (code "113") (name "unconnected-(U1-PC9-PadP40)") (class "Default")
      (node (ref "U1") (pin "P40") (pinfunction "PC9_P40") (pintype "bidirectional"))
    )
    (net (code "114") (name "unconnected-(U1-PC12-PadP53)") (class "Default")
      (node (ref "U1") (pin "P53") (pinfunction "PC12_P53") (pintype "bidirectional"))
    )
    (net (code "115") (name "unconnected-(U1-PC13-PadP2)") (class "Default")
      (node (ref "U1") (pin "P2") (pinfunction "PC13_P2") (pintype "bidirectional"))
    )
    (net (code "116") (name "unconnected-(U1-PC14(OSC32_IN)-PadP3)") (class "Default")
      (node (ref "U1") (pin "P3") (pinfunction "PC14(OSC32_IN)_P3") (pintype "bidirectional"))
    )
    (net (code "117") (name "unconnected-(U1-PC15(OSC32_OUT)-PadP4)") (class "Default")
      (node (ref "U1") (pin "P4") (pinfunction "PC15(OSC32_OUT)_P4") (pintype "bidirectional"))
    )
    (net (code "118") (name "unconnected-(U1-PD2-PadP54)") (class "Default")
      (node (ref "U1") (pin "P54") (pinfunction "PD2_P54") (pintype "bidirectional"))
    )
    (net (code "119") (name "unconnected-(U1-PH0(OSC_IN)-PadP5)") (class "Default")
      (node (ref "U1") (pin "P5") (pinfunction "PH0(OSC_IN)_P5") (pintype "bidirectional"))
    )
    (net (code "120") (name "unconnected-(U1-PH1(OSC_OUT)-PadP6)") (class "Default")
      (node (ref "U1") (pin "P6") (pinfunction "PH1(OSC_OUT)_P6") (pintype "bidirectional"))
    )
    (net (code "121") (name "unconnected-(U1-VBAT-PadP1)") (class "Default")
      (node (ref "U1") (pin "P1") (pinfunction "VBAT_P1") (pintype "bidirectional"))
    )
  )
)
